# Schematicauto.net
KiCad netlist of a schematic drawn in EAGLE
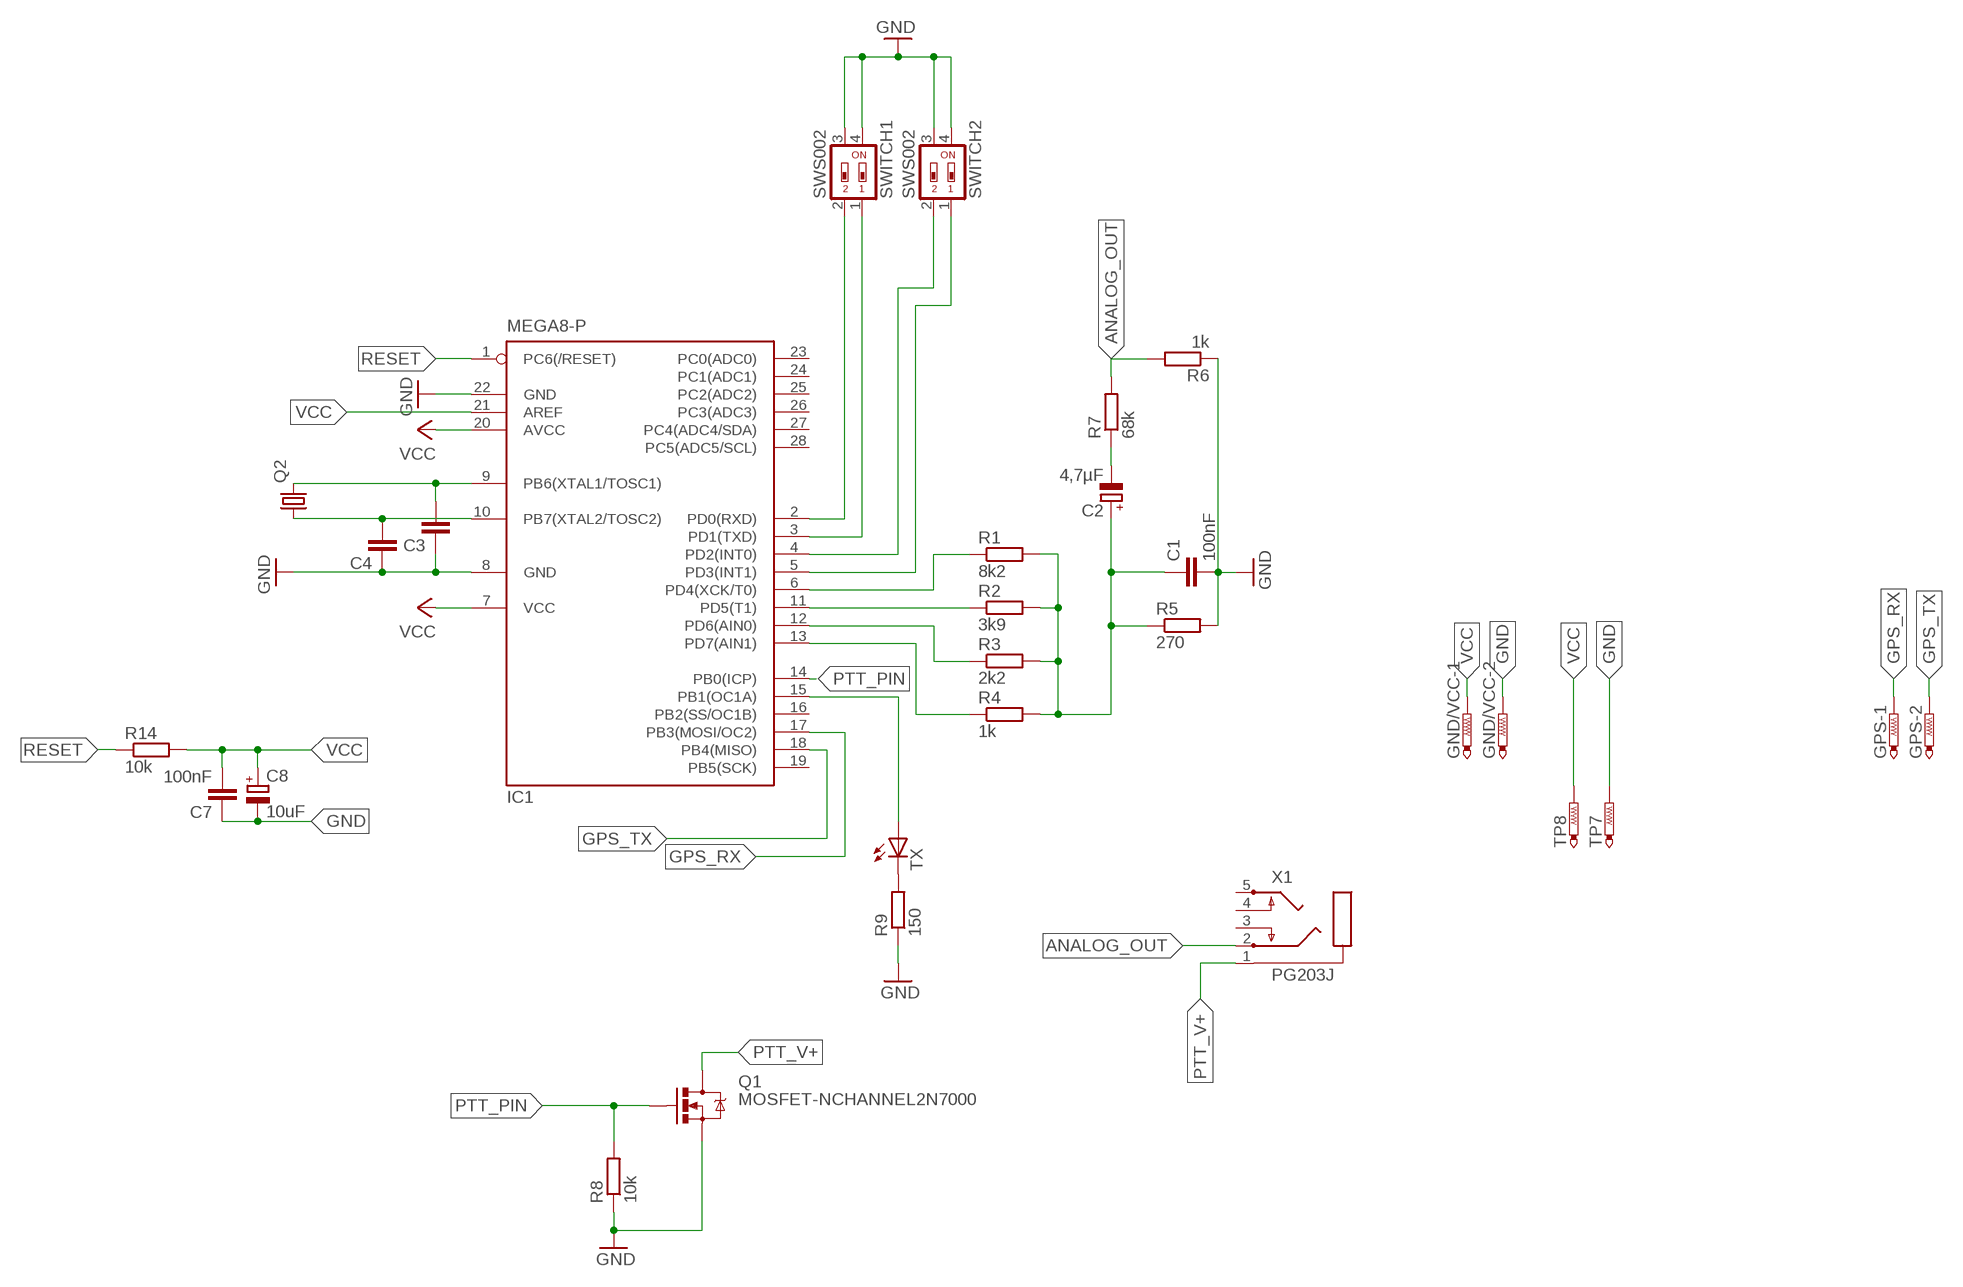
[diagram p0: schematic, sheet 1]

(export (version "E")
  (design (tool "Eeschema 10.0.6"))
  (components
    (comp (ref "C1")
      (value "100nF")
      (footprint "eagle-import:C025-025X050")
      (libsource (lib "eagle-import") (part "C-EU025-025X050"))
    )
    (comp (ref "C2")
      (value "4,7µF")
      (footprint "eagle-import:E2-4")
      (libsource (lib "eagle-import") (part "CPOL-EUE2-4"))
    )
    (comp (ref "C3")
      (value "C-EU025-025X050")
      (footprint "eagle-import:C025-025X050")
      (libsource (lib "eagle-import") (part "C-EU025-025X050"))
    )
    (comp (ref "C4")
      (value "C-EU025-025X050")
      (footprint "eagle-import:C025-025X050")
      (libsource (lib "eagle-import") (part "C-EU025-025X050"))
    )
    (comp (ref "C7")
      (value "100nF")
      (footprint "eagle-import:C050-030X075")
      (libsource (lib "eagle-import") (part "resistor_C-EU050-030X075"))
    )
    (comp (ref "C8")
      (value "10uF")
      (footprint "eagle-import:TT5D9")
      (libsource (lib "eagle-import") (part "CPOL-EUTT5D9"))
    )
    (comp (ref "GND/VCC")
      (value "PTR2")
      (footprint "eagle-import:P2-38-17")
      (libsource (lib "eagle-import") (part "PTR2"))
    )
    (comp (ref "GPS")
      (value "PTR2")
      (footprint "eagle-import:P2-38-17")
      (libsource (lib "eagle-import") (part "PTR2"))
    )
    (comp (ref "IC1")
      (value "MEGA8-P")
      (footprint "eagle-import:DIL28-3")
      (libsource (lib "eagle-import") (part "MEGA8-P"))
    )
    (comp (ref "Q1")
      (value "MOSFET-NCHANNEL2N7000")
      (footprint "eagle-import:TO-92")
      (libsource (lib "eagle-import") (part "MOSFET-NCHANNEL2N7000"))
    )
    (comp (ref "Q2")
      (value "CRYSTALHC49S")
      (footprint "eagle-import:HC49_S")
      (libsource (lib "eagle-import") (part "CRYSTALHC49S"))
    )
    (comp (ref "R1")
      (value "8k2")
      (footprint "eagle-import:0207_12")
      (libsource (lib "eagle-import") (part "R-EU_0207/12"))
    )
    (comp (ref "R2")
      (value "3k9")
      (footprint "eagle-import:0207_12")
      (libsource (lib "eagle-import") (part "R-EU_0207/12"))
    )
    (comp (ref "R3")
      (value "2k2")
      (footprint "eagle-import:0207_12")
      (libsource (lib "eagle-import") (part "R-EU_0207/12"))
    )
    (comp (ref "R4")
      (value "1k")
      (footprint "eagle-import:0207_12")
      (libsource (lib "eagle-import") (part "R-EU_0207/12"))
    )
    (comp (ref "R5")
      (value "270")
      (footprint "eagle-import:0207_12")
      (libsource (lib "eagle-import") (part "R-EU_0207/12"))
    )
    (comp (ref "R6")
      (value "1k")
      (footprint "eagle-import:0207_12")
      (libsource (lib "eagle-import") (part "R-EU_0207/12"))
    )
    (comp (ref "R7")
      (value "68k")
      (footprint "eagle-import:0207_12")
      (libsource (lib "eagle-import") (part "R-EU_0207/12"))
    )
    (comp (ref "R8")
      (value "10k")
      (footprint "eagle-import:0207_12")
      (libsource (lib "eagle-import") (part "R-EU_0207/12"))
    )
    (comp (ref "R9")
      (value "150")
      (footprint "eagle-import:0207_12")
      (libsource (lib "eagle-import") (part "resistor_R-EU_0207/12"))
    )
    (comp (ref "R14")
      (value "10k")
      (footprint "eagle-import:0207_12")
      (libsource (lib "eagle-import") (part "resistor_R-EU_0207/12"))
    )
    (comp (ref "SWITCH1")
      (value "SWS002")
      (footprint "eagle-import:SMS-002")
      (libsource (lib "eagle-import") (part "SWS002"))
    )
    (comp (ref "SWITCH2")
      (value "SWS002")
      (footprint "eagle-import:SMS-002")
      (libsource (lib "eagle-import") (part "SWS002"))
    )
    (comp (ref "TP7")
      (value "PTR1PAD1-20Y")
      (footprint "eagle-import:P1-20Y")
      (libsource (lib "eagle-import") (part "PTR1PAD1-20Y"))
    )
    (comp (ref "TP8")
      (value "PTR1PAD1-20Y")
      (footprint "eagle-import:P1-20Y")
      (libsource (lib "eagle-import") (part "PTR1PAD1-20Y"))
    )
    (comp (ref "TX")
      (value "LED5MM")
      (footprint "eagle-import:LED5MM")
      (libsource (lib "eagle-import") (part "LED5MM"))
    )
    (comp (ref "X1")
      (value "PG203J")
      (footprint "eagle-import:PG203J")
      (libsource (lib "eagle-import") (part "PG203J"))
    )
  )
  (nets
    (net (code "1") (name "ANALOG_OUT") (class "Default")
      (node (ref "R6") (pin "2") (pinfunction "2_2") (pintype "passive"))
      (node (ref "R7") (pin "2") (pinfunction "2_2") (pintype "passive"))
      (node (ref "X1") (pin "2") (pinfunction "2_2") (pintype "passive"))
    )
    (net (code "2") (name "GND") (class "Default")
      (node (ref "C1") (pin "2") (pinfunction "2_2") (pintype "passive"))
      (node (ref "C3") (pin "1") (pinfunction "1_1") (pintype "passive"))
      (node (ref "C4") (pin "1") (pinfunction "1_1") (pintype "passive"))
      (node (ref "C7") (pin "1") (pinfunction "1_1") (pintype "passive"))
      (node (ref "C8") (pin "-") (pinfunction "-_-") (pintype "passive"))
      (node (ref "GND/VCC") (pin "TP-2") (pinfunction "TP_TP-2") (pintype "input"))
      (node (ref "IC1") (pin "22") (pinfunction "GND_22") (pintype "power_in"))
      (node (ref "IC1") (pin "8") (pinfunction "GND_8") (pintype "power_in"))
      (node (ref "Q1") (pin "1") (pinfunction "S_1") (pintype "passive"))
      (node (ref "R5") (pin "2") (pinfunction "2_2") (pintype "passive"))
      (node (ref "R6") (pin "1") (pinfunction "1_1") (pintype "passive"))
      (node (ref "R8") (pin "1") (pinfunction "1_1") (pintype "passive"))
      (node (ref "R9") (pin "1") (pinfunction "1_1") (pintype "passive"))
      (node (ref "SWITCH1") (pin "3") (pinfunction "3_3") (pintype "passive"))
      (node (ref "SWITCH1") (pin "4") (pinfunction "4_4") (pintype "passive"))
      (node (ref "SWITCH2") (pin "3") (pinfunction "3_3") (pintype "passive"))
      (node (ref "SWITCH2") (pin "4") (pinfunction "4_4") (pintype "passive"))
      (node (ref "TP7") (pin "TP") (pinfunction "TP_TP") (pintype "input"))
    )
    (net (code "3") (name "GPS_RX") (class "Default")
      (node (ref "GPS") (pin "TP-1") (pinfunction "TP_TP-1") (pintype "input"))
      (node (ref "IC1") (pin "17") (pinfunction "PB3(MOSI/OC2)_17") (pintype "bidirectional"))
    )
    (net (code "4") (name "GPS_TX") (class "Default")
      (node (ref "GPS") (pin "TP-2") (pinfunction "TP_TP-2") (pintype "input"))
      (node (ref "IC1") (pin "18") (pinfunction "PB4(MISO)_18") (pintype "bidirectional"))
    )
    (net (code "5") (name "Net-(C1-Pad1)") (class "Default")
      (node (ref "C1") (pin "1") (pinfunction "1_1") (pintype "passive"))
      (node (ref "C2") (pin "+") (pinfunction "+_+") (pintype "passive"))
      (node (ref "R1") (pin "2") (pinfunction "2_2") (pintype "passive"))
      (node (ref "R2") (pin "2") (pinfunction "2_2") (pintype "passive"))
      (node (ref "R3") (pin "2") (pinfunction "2_2") (pintype "passive"))
      (node (ref "R4") (pin "2") (pinfunction "2_2") (pintype "passive"))
      (node (ref "R5") (pin "1") (pinfunction "1_1") (pintype "passive"))
    )
    (net (code "6") (name "Net-(C2-Pad-)") (class "Default")
      (node (ref "C2") (pin "-") (pinfunction "-_-") (pintype "passive"))
      (node (ref "R7") (pin "1") (pinfunction "1_1") (pintype "passive"))
    )
    (net (code "7") (name "Net-(IC1-PB1(OC1A))") (class "Default")
      (node (ref "IC1") (pin "15") (pinfunction "PB1(OC1A)_15") (pintype "bidirectional"))
      (node (ref "TX") (pin "A") (pinfunction "A_A") (pintype "passive"))
    )
    (net (code "8") (name "Net-(IC1-PB6(XTAL1{slash}TOSC1))") (class "Default")
      (node (ref "C3") (pin "2") (pinfunction "2_2") (pintype "passive"))
      (node (ref "IC1") (pin "9") (pinfunction "PB6(XTAL1/TOSC1)_9") (pintype "bidirectional"))
      (node (ref "Q2") (pin "2") (pinfunction "2_2") (pintype "passive"))
    )
    (net (code "9") (name "Net-(IC1-PB7(XTAL2{slash}TOSC2))") (class "Default")
      (node (ref "C4") (pin "2") (pinfunction "2_2") (pintype "passive"))
      (node (ref "IC1") (pin "10") (pinfunction "PB7(XTAL2/TOSC2)_10") (pintype "bidirectional"))
      (node (ref "Q2") (pin "1") (pinfunction "1_1") (pintype "passive"))
    )
    (net (code "10") (name "Net-(IC1-PD0(RXD))") (class "Default")
      (node (ref "IC1") (pin "2") (pinfunction "PD0(RXD)_2") (pintype "bidirectional"))
      (node (ref "SWITCH1") (pin "2") (pinfunction "2_2") (pintype "passive"))
    )
    (net (code "11") (name "Net-(IC1-PD1(TXD))") (class "Default")
      (node (ref "IC1") (pin "3") (pinfunction "PD1(TXD)_3") (pintype "bidirectional"))
      (node (ref "SWITCH1") (pin "1") (pinfunction "1_1") (pintype "passive"))
    )
    (net (code "12") (name "Net-(IC1-PD2(INT0))") (class "Default")
      (node (ref "IC1") (pin "4") (pinfunction "PD2(INT0)_4") (pintype "bidirectional"))
      (node (ref "SWITCH2") (pin "2") (pinfunction "2_2") (pintype "passive"))
    )
    (net (code "13") (name "Net-(IC1-PD3(INT1))") (class "Default")
      (node (ref "IC1") (pin "5") (pinfunction "PD3(INT1)_5") (pintype "bidirectional"))
      (node (ref "SWITCH2") (pin "1") (pinfunction "1_1") (pintype "passive"))
    )
    (net (code "14") (name "Net-(IC1-PD4(XCK{slash}T0))") (class "Default")
      (node (ref "IC1") (pin "6") (pinfunction "PD4(XCK/T0)_6") (pintype "bidirectional"))
      (node (ref "R1") (pin "1") (pinfunction "1_1") (pintype "passive"))
    )
    (net (code "15") (name "Net-(IC1-PD5(T1))") (class "Default")
      (node (ref "IC1") (pin "11") (pinfunction "PD5(T1)_11") (pintype "bidirectional"))
      (node (ref "R2") (pin "1") (pinfunction "1_1") (pintype "passive"))
    )
    (net (code "16") (name "Net-(IC1-PD6(AIN0))") (class "Default")
      (node (ref "IC1") (pin "12") (pinfunction "PD6(AIN0)_12") (pintype "bidirectional"))
      (node (ref "R3") (pin "1") (pinfunction "1_1") (pintype "passive"))
    )
    (net (code "17") (name "Net-(IC1-PD7(AIN1))") (class "Default")
      (node (ref "IC1") (pin "13") (pinfunction "PD7(AIN1)_13") (pintype "bidirectional"))
      (node (ref "R4") (pin "1") (pinfunction "1_1") (pintype "passive"))
    )
    (net (code "18") (name "Net-(TX-C)") (class "Default")
      (node (ref "R9") (pin "2") (pinfunction "2_2") (pintype "passive"))
      (node (ref "TX") (pin "K") (pinfunction "C_K") (pintype "passive"))
    )
    (net (code "19") (name "PTT_PIN") (class "Default")
      (node (ref "IC1") (pin "14") (pinfunction "PB0(ICP)_14") (pintype "bidirectional"))
      (node (ref "Q1") (pin "2") (pinfunction "G_2") (pintype "passive"))
      (node (ref "R8") (pin "2") (pinfunction "2_2") (pintype "passive"))
    )
    (net (code "20") (name "PTT_V+") (class "Default")
      (node (ref "Q1") (pin "3") (pinfunction "D_3") (pintype "passive"))
      (node (ref "X1") (pin "1") (pinfunction "1_1") (pintype "passive"))
    )
    (net (code "21") (name "RESET") (class "Default")
      (node (ref "IC1") (pin "1") (pinfunction "PC6(/RESET)_1") (pintype "bidirectional"))
      (node (ref "R14") (pin "1") (pinfunction "1_1") (pintype "passive"))
    )
    (net (code "22") (name "VCC") (class "Default")
      (node (ref "C7") (pin "2") (pinfunction "2_2") (pintype "passive"))
      (node (ref "C8") (pin "+") (pinfunction "+_+") (pintype "passive"))
      (node (ref "GND/VCC") (pin "TP-1") (pinfunction "TP_TP-1") (pintype "input"))
      (node (ref "IC1") (pin "20") (pinfunction "AVCC_20") (pintype "power_in"))
      (node (ref "IC1") (pin "21") (pinfunction "AREF_21") (pintype "passive"))
      (node (ref "IC1") (pin "7") (pinfunction "VCC_7") (pintype "power_in"))
      (node (ref "R14") (pin "2") (pinfunction "2_2") (pintype "passive"))
      (node (ref "TP8") (pin "TP") (pinfunction "TP_TP") (pintype "input"))
    )
    (net (code "23") (name "unconnected-(IC1-PB2(SS{slash}OC1B)-Pad16)") (class "Default")
      (node (ref "IC1") (pin "16") (pinfunction "PB2(SS/OC1B)_16") (pintype "bidirectional"))
    )
    (net (code "24") (name "unconnected-(IC1-PB5(SCK)-Pad19)") (class "Default")
      (node (ref "IC1") (pin "19") (pinfunction "PB5(SCK)_19") (pintype "bidirectional"))
    )
    (net (code "25") (name "unconnected-(IC1-PC0(ADC0)-Pad23)") (class "Default")
      (node (ref "IC1") (pin "23") (pinfunction "PC0(ADC0)_23") (pintype "bidirectional"))
    )
    (net (code "26") (name "unconnected-(IC1-PC1(ADC1)-Pad24)") (class "Default")
      (node (ref "IC1") (pin "24") (pinfunction "PC1(ADC1)_24") (pintype "bidirectional"))
    )
    (net (code "27") (name "unconnected-(IC1-PC2(ADC2)-Pad25)") (class "Default")
      (node (ref "IC1") (pin "25") (pinfunction "PC2(ADC2)_25") (pintype "bidirectional"))
    )
    (net (code "28") (name "unconnected-(IC1-PC3(ADC3)-Pad26)") (class "Default")
      (node (ref "IC1") (pin "26") (pinfunction "PC3(ADC3)_26") (pintype "bidirectional"))
    )
    (net (code "29") (name "unconnected-(IC1-PC4(ADC4{slash}SDA)-Pad27)") (class "Default")
      (node (ref "IC1") (pin "27") (pinfunction "PC4(ADC4/SDA)_27") (pintype "bidirectional"))
    )
    (net (code "30") (name "unconnected-(IC1-PC5(ADC5{slash}SCL)-Pad28)") (class "Default")
      (node (ref "IC1") (pin "28") (pinfunction "PC5(ADC5/SCL)_28") (pintype "bidirectional"))
    )
    (net (code "31") (name "unconnected-(X1-Pad3)") (class "Default")
      (node (ref "X1") (pin "3") (pinfunction "3_3") (pintype "passive"))
    )
    (net (code "32") (name "unconnected-(X1-Pad4)") (class "Default")
      (node (ref "X1") (pin "4") (pinfunction "4_4") (pintype "passive"))
    )
    (net (code "33") (name "unconnected-(X1-Pad5)") (class "Default")
      (node (ref "X1") (pin "5") (pinfunction "5_5") (pintype "passive"))
    )
  )
)
